# Esquem_tico_circuito.net
KiCad netlist of a schematic drawn in EasyEDA
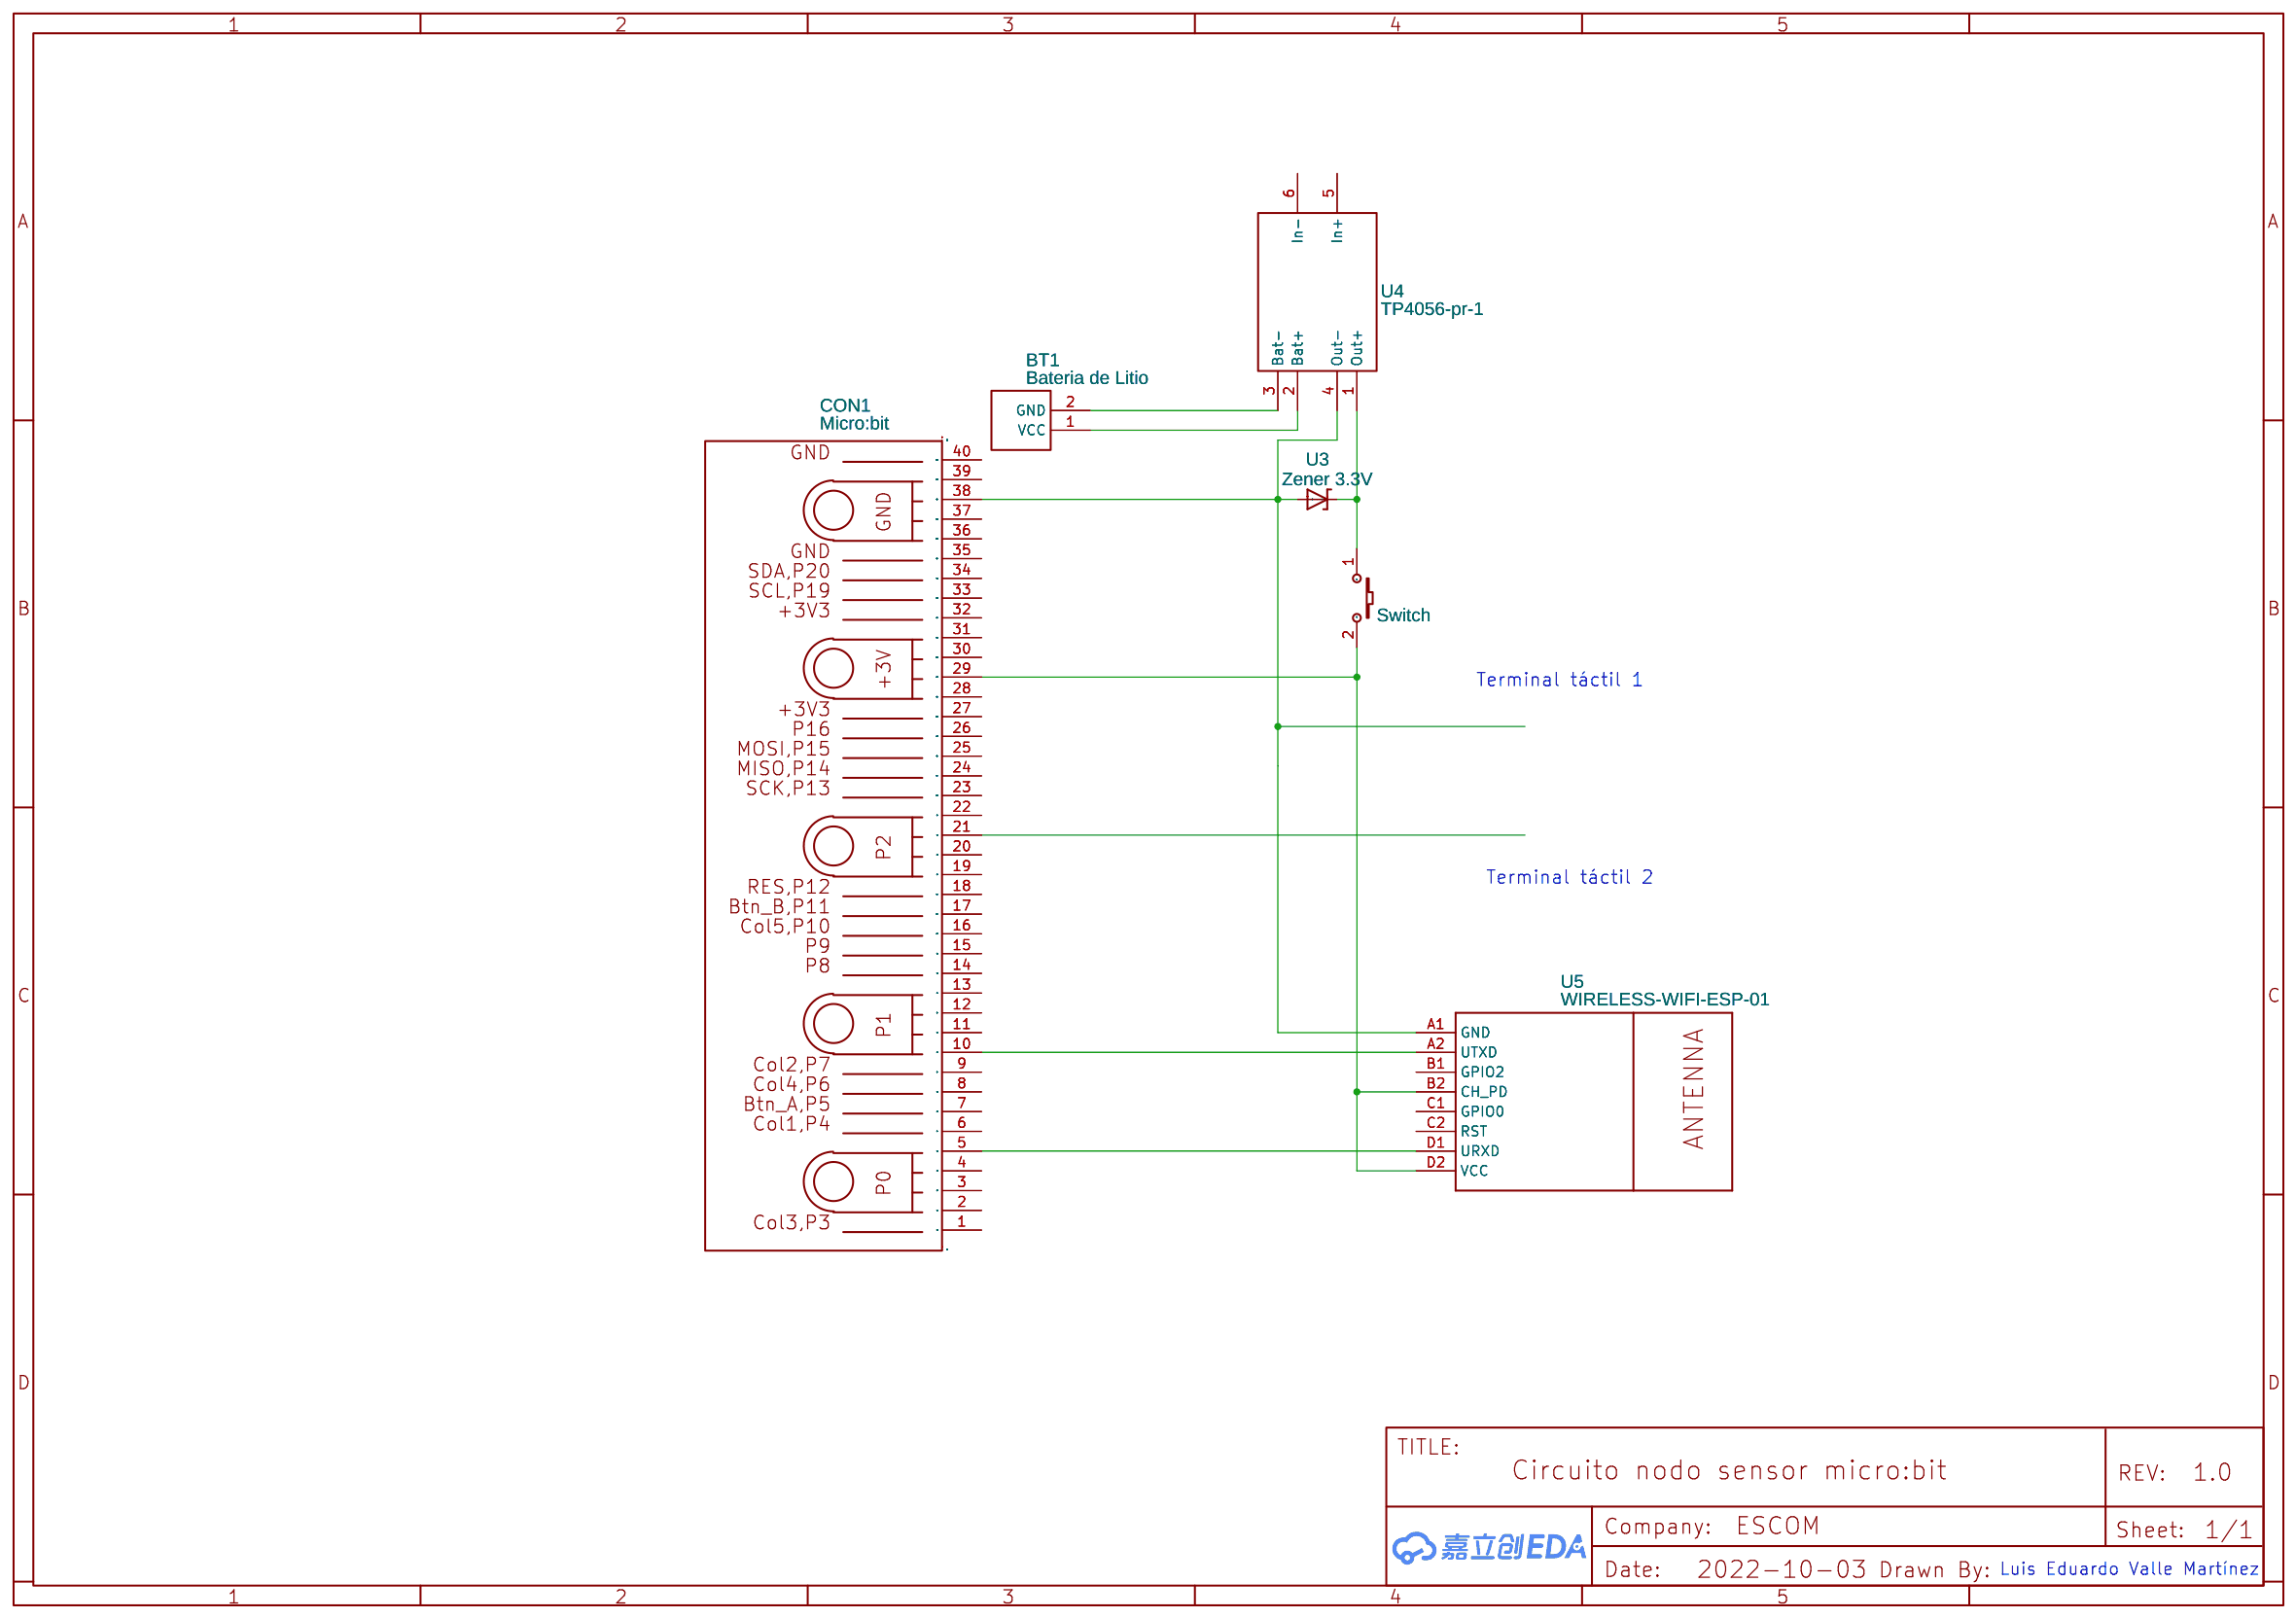
[diagram p0: schematic sheet]

(export (version "E")
  (design (tool "Eeschema 10.0.6"))
  (components
    (comp (ref "BT1")
      (value "Bateria de Litio")
      (fields
        (field (name "BOM_Manufacturer Part") "No.52Section side by side battery box")
        (field (name "BOM_Supplier Part") "C5404")
      )
      (libsource (lib "") (part "No.52Section side by side battery box"))
    )
    (comp (ref "CON1")
      (value "Micro:bit")
      (libsource (lib "") (part "CYLCONN-MICROBIT-V2-EDGE-40P-180DEG_1"))
    )
    (comp (ref "KEY1")
      (value "Switch")
      (fields
        (field (name "BOM_Manufacturer Part") "K2-1107ST-A4SW-06")
        (field (name "BOM_Supplier Part") "C118141")
      )
      (libsource (lib "") (part "K2-3.6×6.1_SMD"))
    )
    (comp (ref "U3") (value "Zener 3.3V") (libsource (lib "") (part "DIODE-ZENER")))
    (comp (ref "U4") (value "TP4056-pr-1") (libsource (lib "") (part "TP4056-pr-1")))
    (comp (ref "U5") (value "WIRELESS-WIFI-ESP-01") (libsource (lib "") (part "WIRELESS-WIFI-ESP-01")))
  )
  (nets
    (net (code "1") (name "Net-(BT1-GND)") (class "Default")
      (node (ref "BT1") (pin "2") (pinfunction "GND_2") (pintype "unspecified"))
      (node (ref "U4") (pin "3") (pinfunction "Bat-_3") (pintype "unspecified"))
    )
    (net (code "2") (name "Net-(BT1-VCC)") (class "Default")
      (node (ref "BT1") (pin "1") (pinfunction "VCC_1") (pintype "unspecified"))
      (node (ref "U4") (pin "2") (pinfunction "Bat+_2") (pintype "unspecified"))
    )
    (net (code "3") (name "Net-(U3-A)") (class "Default")
      (node (ref "CON1") (pin "38") (pinfunction "GND_38") (pintype "unspecified"))
      (node (ref "U3") (pin "P$2") (pinfunction "A_P$2") (pintype "unspecified"))
      (node (ref "U4") (pin "4") (pinfunction "Out-_4") (pintype "unspecified"))
      (node (ref "U5") (pin "A1") (pinfunction "GND_A1") (pintype "passive"))
    )
    (net (code "4") (name "Net-(U3-C)") (class "Default")
      (node (ref "KEY1") (pin "1") (pinfunction "1_1") (pintype "unspecified"))
      (node (ref "U3") (pin "P$1") (pinfunction "C_P$1") (pintype "unspecified"))
      (node (ref "U4") (pin "1") (pinfunction "Out+_1") (pintype "unspecified"))
    )
    (net (code "5") (name "Net-(U5-CH_PD)") (class "Default")
      (node (ref "CON1") (pin "29") (pinfunction "+3V3_29") (pintype "unspecified"))
      (node (ref "KEY1") (pin "2") (pinfunction "2_2") (pintype "unspecified"))
      (node (ref "U5") (pin "B2") (pinfunction "CH_PD_B2") (pintype "unspecified"))
      (node (ref "U5") (pin "D2") (pinfunction "VCC_D2") (pintype "passive"))
    )
    (net (code "6") (name "Net-(U5-URXD)") (class "Default")
      (node (ref "CON1") (pin "5") (pinfunction "P0_5") (pintype "unspecified"))
      (node (ref "U5") (pin "D1") (pinfunction "URXD_D1") (pintype "unspecified"))
    )
    (net (code "7") (name "Net-(U5-UTXD)") (class "Default")
      (node (ref "CON1") (pin "10") (pinfunction "P1_10") (pintype "unspecified"))
      (node (ref "U5") (pin "A2") (pinfunction "UTXD_A2") (pintype "unspecified"))
    )
    (net (code "8") (name "unconnected-(CON1-+3V3-Pad27)") (class "Default")
      (node (ref "CON1") (pin "27") (pinfunction "+3V3_27") (pintype "unspecified"))
    )
    (net (code "9") (name "unconnected-(CON1-+3V3-Pad28)") (class "Default")
      (node (ref "CON1") (pin "28") (pinfunction "+3V3_28") (pintype "unspecified"))
    )
    (net (code "10") (name "unconnected-(CON1-+3V3-Pad30)") (class "Default")
      (node (ref "CON1") (pin "30") (pinfunction "+3V3_30") (pintype "unspecified"))
    )
    (net (code "11") (name "unconnected-(CON1-+3V3-Pad31)") (class "Default")
      (node (ref "CON1") (pin "31") (pinfunction "+3V3_31") (pintype "unspecified"))
    )
    (net (code "12") (name "unconnected-(CON1-+3V3-Pad32)") (class "Default")
      (node (ref "CON1") (pin "32") (pinfunction "+3V3_32") (pintype "unspecified"))
    )
    (net (code "13") (name "unconnected-(CON1-GND-Pad35)") (class "Default")
      (node (ref "CON1") (pin "35") (pinfunction "GND_35") (pintype "unspecified"))
    )
    (net (code "14") (name "unconnected-(CON1-GND-Pad36)") (class "Default")
      (node (ref "CON1") (pin "36") (pinfunction "GND_36") (pintype "unspecified"))
    )
    (net (code "15") (name "unconnected-(CON1-GND-Pad37)") (class "Default")
      (node (ref "CON1") (pin "37") (pinfunction "GND_37") (pintype "unspecified"))
    )
    (net (code "16") (name "unconnected-(CON1-GND-Pad39)") (class "Default")
      (node (ref "CON1") (pin "39") (pinfunction "GND_39") (pintype "unspecified"))
    )
    (net (code "17") (name "unconnected-(CON1-GND-Pad40)") (class "Default")
      (node (ref "CON1") (pin "40") (pinfunction "GND_40") (pintype "unspecified"))
    )
    (net (code "18") (name "unconnected-(CON1-NC41-Pad41)") (class "Default")
      (node (ref "CON1") (pin "41") (pinfunction "NC41_41") (pintype "unspecified"))
    )
    (net (code "19") (name "unconnected-(CON1-NC42-Pad42)") (class "Default")
      (node (ref "CON1") (pin "42") (pinfunction "NC42_42") (pintype "unspecified"))
    )
    (net (code "20") (name "unconnected-(CON1-P0-Pad2)") (class "Default")
      (node (ref "CON1") (pin "2") (pinfunction "P0_2") (pintype "unspecified"))
    )
    (net (code "21") (name "unconnected-(CON1-P0-Pad3)") (class "Default")
      (node (ref "CON1") (pin "3") (pinfunction "P0_3") (pintype "unspecified"))
    )
    (net (code "22") (name "unconnected-(CON1-P0-Pad4)") (class "Default")
      (node (ref "CON1") (pin "4") (pinfunction "P0_4") (pintype "unspecified"))
    )
    (net (code "23") (name "unconnected-(CON1-P1-Pad11)") (class "Default")
      (node (ref "CON1") (pin "11") (pinfunction "P1_11") (pintype "unspecified"))
    )
    (net (code "24") (name "unconnected-(CON1-P1-Pad12)") (class "Default")
      (node (ref "CON1") (pin "12") (pinfunction "P1_12") (pintype "unspecified"))
    )
    (net (code "25") (name "unconnected-(CON1-P1-Pad13)") (class "Default")
      (node (ref "CON1") (pin "13") (pinfunction "P1_13") (pintype "unspecified"))
    )
    (net (code "26") (name "unconnected-(CON1-P2-Pad19)") (class "Default")
      (node (ref "CON1") (pin "19") (pinfunction "P2_19") (pintype "unspecified"))
    )
    (net (code "27") (name "unconnected-(CON1-P2-Pad20)") (class "Default")
      (node (ref "CON1") (pin "20") (pinfunction "P2_20") (pintype "unspecified"))
    )
    (net (code "28") (name "unconnected-(CON1-P2-Pad21)") (class "Default")
      (node (ref "CON1") (pin "21") (pinfunction "P2_21") (pintype "unspecified"))
    )
    (net (code "29") (name "unconnected-(CON1-P2-Pad22)") (class "Default")
      (node (ref "CON1") (pin "22") (pinfunction "P2_22") (pintype "unspecified"))
    )
    (net (code "30") (name "unconnected-(CON1-P3-Pad1)") (class "Default")
      (node (ref "CON1") (pin "1") (pinfunction "P3_1") (pintype "unspecified"))
    )
    (net (code "31") (name "unconnected-(CON1-P4-Pad6)") (class "Default")
      (node (ref "CON1") (pin "6") (pinfunction "P4_6") (pintype "unspecified"))
    )
    (net (code "32") (name "unconnected-(CON1-P5-Pad7)") (class "Default")
      (node (ref "CON1") (pin "7") (pinfunction "P5_7") (pintype "unspecified"))
    )
    (net (code "33") (name "unconnected-(CON1-P6-Pad8)") (class "Default")
      (node (ref "CON1") (pin "8") (pinfunction "P6_8") (pintype "unspecified"))
    )
    (net (code "34") (name "unconnected-(CON1-P7-Pad9)") (class "Default")
      (node (ref "CON1") (pin "9") (pinfunction "P7_9") (pintype "unspecified"))
    )
    (net (code "35") (name "unconnected-(CON1-P8-Pad14)") (class "Default")
      (node (ref "CON1") (pin "14") (pinfunction "P8_14") (pintype "unspecified"))
    )
    (net (code "36") (name "unconnected-(CON1-P9-Pad15)") (class "Default")
      (node (ref "CON1") (pin "15") (pinfunction "P9_15") (pintype "unspecified"))
    )
    (net (code "37") (name "unconnected-(CON1-P10-Pad16)") (class "Default")
      (node (ref "CON1") (pin "16") (pinfunction "P10_16") (pintype "unspecified"))
    )
    (net (code "38") (name "unconnected-(CON1-P11-Pad17)") (class "Default")
      (node (ref "CON1") (pin "17") (pinfunction "P11_17") (pintype "unspecified"))
    )
    (net (code "39") (name "unconnected-(CON1-P12-Pad18)") (class "Default")
      (node (ref "CON1") (pin "18") (pinfunction "P12_18") (pintype "unspecified"))
    )
    (net (code "40") (name "unconnected-(CON1-P13-Pad23)") (class "Default")
      (node (ref "CON1") (pin "23") (pinfunction "P13_23") (pintype "unspecified"))
    )
    (net (code "41") (name "unconnected-(CON1-P14-Pad24)") (class "Default")
      (node (ref "CON1") (pin "24") (pinfunction "P14_24") (pintype "unspecified"))
    )
    (net (code "42") (name "unconnected-(CON1-P15-Pad25)") (class "Default")
      (node (ref "CON1") (pin "25") (pinfunction "P15_25") (pintype "unspecified"))
    )
    (net (code "43") (name "unconnected-(CON1-P16-Pad26)") (class "Default")
      (node (ref "CON1") (pin "26") (pinfunction "P16_26") (pintype "unspecified"))
    )
    (net (code "44") (name "unconnected-(CON1-P19-Pad33)") (class "Default")
      (node (ref "CON1") (pin "33") (pinfunction "P19_33") (pintype "unspecified"))
    )
    (net (code "45") (name "unconnected-(CON1-P20-Pad34)") (class "Default")
      (node (ref "CON1") (pin "34") (pinfunction "P20_34") (pintype "unspecified"))
    )
    (net (code "46") (name "unconnected-(U4-In+-Pad5)") (class "Default")
      (node (ref "U4") (pin "5") (pinfunction "In+_5") (pintype "unspecified"))
    )
    (net (code "47") (name "unconnected-(U4-In--Pad6)") (class "Default")
      (node (ref "U4") (pin "6") (pinfunction "In-_6") (pintype "unspecified"))
    )
    (net (code "48") (name "unconnected-(U5-GPIO0-PadC1)") (class "Default")
      (node (ref "U5") (pin "C1") (pinfunction "GPIO0_C1") (pintype "unspecified"))
    )
    (net (code "49") (name "unconnected-(U5-GPIO2-PadB1)") (class "Default")
      (node (ref "U5") (pin "B1") (pinfunction "GPIO2_B1") (pintype "unspecified"))
    )
    (net (code "50") (name "unconnected-(U5-RST-PadC2)") (class "Default")
      (node (ref "U5") (pin "C2") (pinfunction "RST_C2") (pintype "unspecified"))
    )
  )
)
